# ADC-ICHANNEL_INPUT.net
KiCad netlist of a schematic drawn in Altium Designer
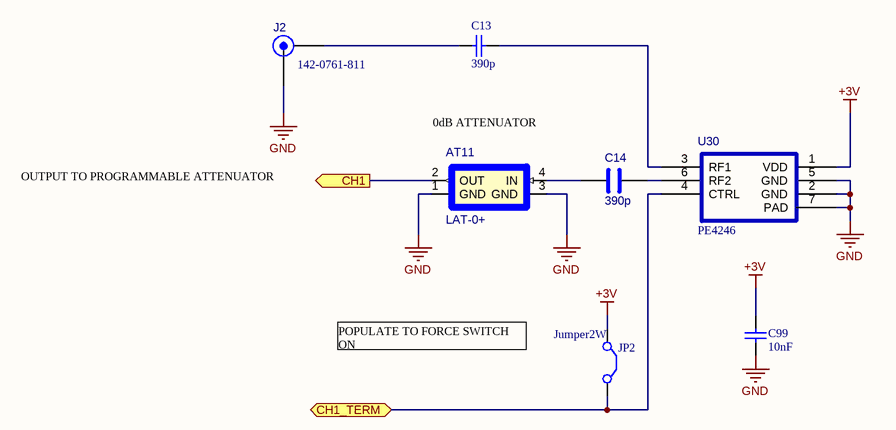
[diagram p0: ADC-ICHANNEL INPUT.SchDoc]

(export (version "E")
  (design (tool "Eeschema 10.0.6"))
  (components
    (comp (ref "AT11")
      (value "~")
      (footprint "MINICIRCUITS_MMM168")
      (description "Fixed Attenuator")
      (fields
        (field (name "MANUFACTURER") "Mini-Circuits")
        (field (name "MANUFACTURER_PN") "LAT-0+")
        (field (name "CREATED_BY") "CT")
        (field (name "CHECKED_BY") "*")
      )
      (libsource (lib "Charles-TEMP") (part "LAT-0+"))
    )
    (comp (ref "C13")
      (value "390p")
      (footprint "CAPC1005X55N")
      (description "Capacitor 0402 SMD")
      (fields (field (name "CREATED_BY") "EDA-ASA") (field (name "CHECKED_BY") "*"))
      (libsource (lib "EDA-Passive") (part "cap0402"))
    )
    (comp (ref "C14")
      (value "390p")
      (footprint "CAPC1005X55N")
      (description "CAP SMD 0603")
      (fields
        (field (name "Comment") "Footprint ???")
        (field (name "CREATED_BY") "*")
        (field (name "CHECKED_BY") "*")
      )
      (libsource (lib "Abdus-TEMP") (part "CAP-0603"))
    )
    (comp (ref "C99")
      (value "10nF")
      (footprint "CAPC1005X55N")
      (description "Capacitor 0402 SMD")
      (fields (field (name "CREATED_BY") "EDA-ASA") (field (name "CHECKED_BY") "*"))
      (libsource (lib "EDA-Passive") (part "cap0402"))
    )
    (comp (ref "J2")
      (value "~")
      (footprint "EDGE_LAUNCH_TH_SMA")
      (description "High Frequency SMA End Lauch Connector")
      (fields
        (field (name "MANUFACTURER") "JOHNSON")
        (field (name "VOLTAGE") "???")
        (field (name "MANUFACTURER_PN") "142-0761-811")
        (field (name "CREATED_BY") "CT")
        (field (name "CHECKED_BY") "*")
      )
      (libsource (lib "Charles-TEMP") (part "142-0761-811"))
    )
    (comp (ref "JP2")
      (value "Jumper2W")
      (footprint "JUMPER")
      (description "Jumper Wire")
      (fields (field (name "PUBLISHER") "Altium Limited"))
      (libsource (lib "EDA-Hardware") (part "Jumper2W"))
    )
    (comp (ref "U30")
      (value "PE4246")
      (footprint "PSON95P300X300X90-7USR")
      (description "Absorptive SPST UltraCMOS RF Switch")
      (fields
        (field (name "MANUFACTURER") "Pergrime Semiconductor")
        (field (name "CREATED_BY") "IN")
        (field (name "CHECKED_BY") "*")
      )
      (libsource (lib "Ishvah-TEMP") (part "PE4246"))
    )
  )
  (nets
    (net (code "1") (name "+3V") (class "Default")
      (node (ref "C99") (pin "1") (pinfunction "1_1") (pintype "passive"))
      (node (ref "JP2") (pin "1") (pinfunction "C1_1") (pintype "passive"))
      (node (ref "U30") (pin "1") (pinfunction "VDD_1") (pintype "passive"))
    )
    (net (code "2") (name "/CH1") (class "Default")
      (node (ref "AT11") (pin "2") (pinfunction "OUT_2") (pintype "output"))
    )
    (net (code "3") (name "/CH1_TERM") (class "Default")
      (node (ref "JP2") (pin "2") (pinfunction "C2_2") (pintype "passive"))
      (node (ref "U30") (pin "4") (pinfunction "CTRL_4") (pintype "passive"))
    )
    (net (code "4") (name "GND") (class "Default")
      (node (ref "AT11") (pin "1") (pinfunction "GND_1") (pintype "power_in"))
      (node (ref "AT11") (pin "3") (pinfunction "GND_3") (pintype "power_in"))
      (node (ref "C99") (pin "2") (pinfunction "2_2") (pintype "passive"))
      (node (ref "J2") (pin "2") (pinfunction "2_2") (pintype "passive"))
      (node (ref "U30") (pin "2") (pinfunction "GND_2") (pintype "passive"))
      (node (ref "U30") (pin "5") (pinfunction "GND_5") (pintype "passive"))
      (node (ref "U30") (pin "7") (pinfunction "PAD_7") (pintype "passive"))
    )
    (net (code "5") (name "Net-(AT11-IN)") (class "Default")
      (node (ref "AT11") (pin "4") (pinfunction "IN_4") (pintype "input"))
      (node (ref "C14") (pin "2") (pinfunction "2_2") (pintype "passive"))
    )
    (net (code "6") (name "Net-(C13-Pad1)") (class "Default")
      (node (ref "C13") (pin "1") (pinfunction "1_1") (pintype "passive"))
      (node (ref "J2") (pin "1") (pinfunction "1_1") (pintype "passive"))
    )
    (net (code "7") (name "Net-(U30-RF1)") (class "Default")
      (node (ref "C13") (pin "2") (pinfunction "2_2") (pintype "passive"))
      (node (ref "U30") (pin "3") (pinfunction "RF1_3") (pintype "passive"))
    )
    (net (code "8") (name "Net-(U30-RF2)") (class "Default")
      (node (ref "C14") (pin "1") (pinfunction "1_1") (pintype "passive"))
      (node (ref "U30") (pin "6") (pinfunction "RF2_6") (pintype "passive"))
    )
  )
)
